# OpenCTD-V02.net
KiCad netlist of a schematic drawn in EAGLE
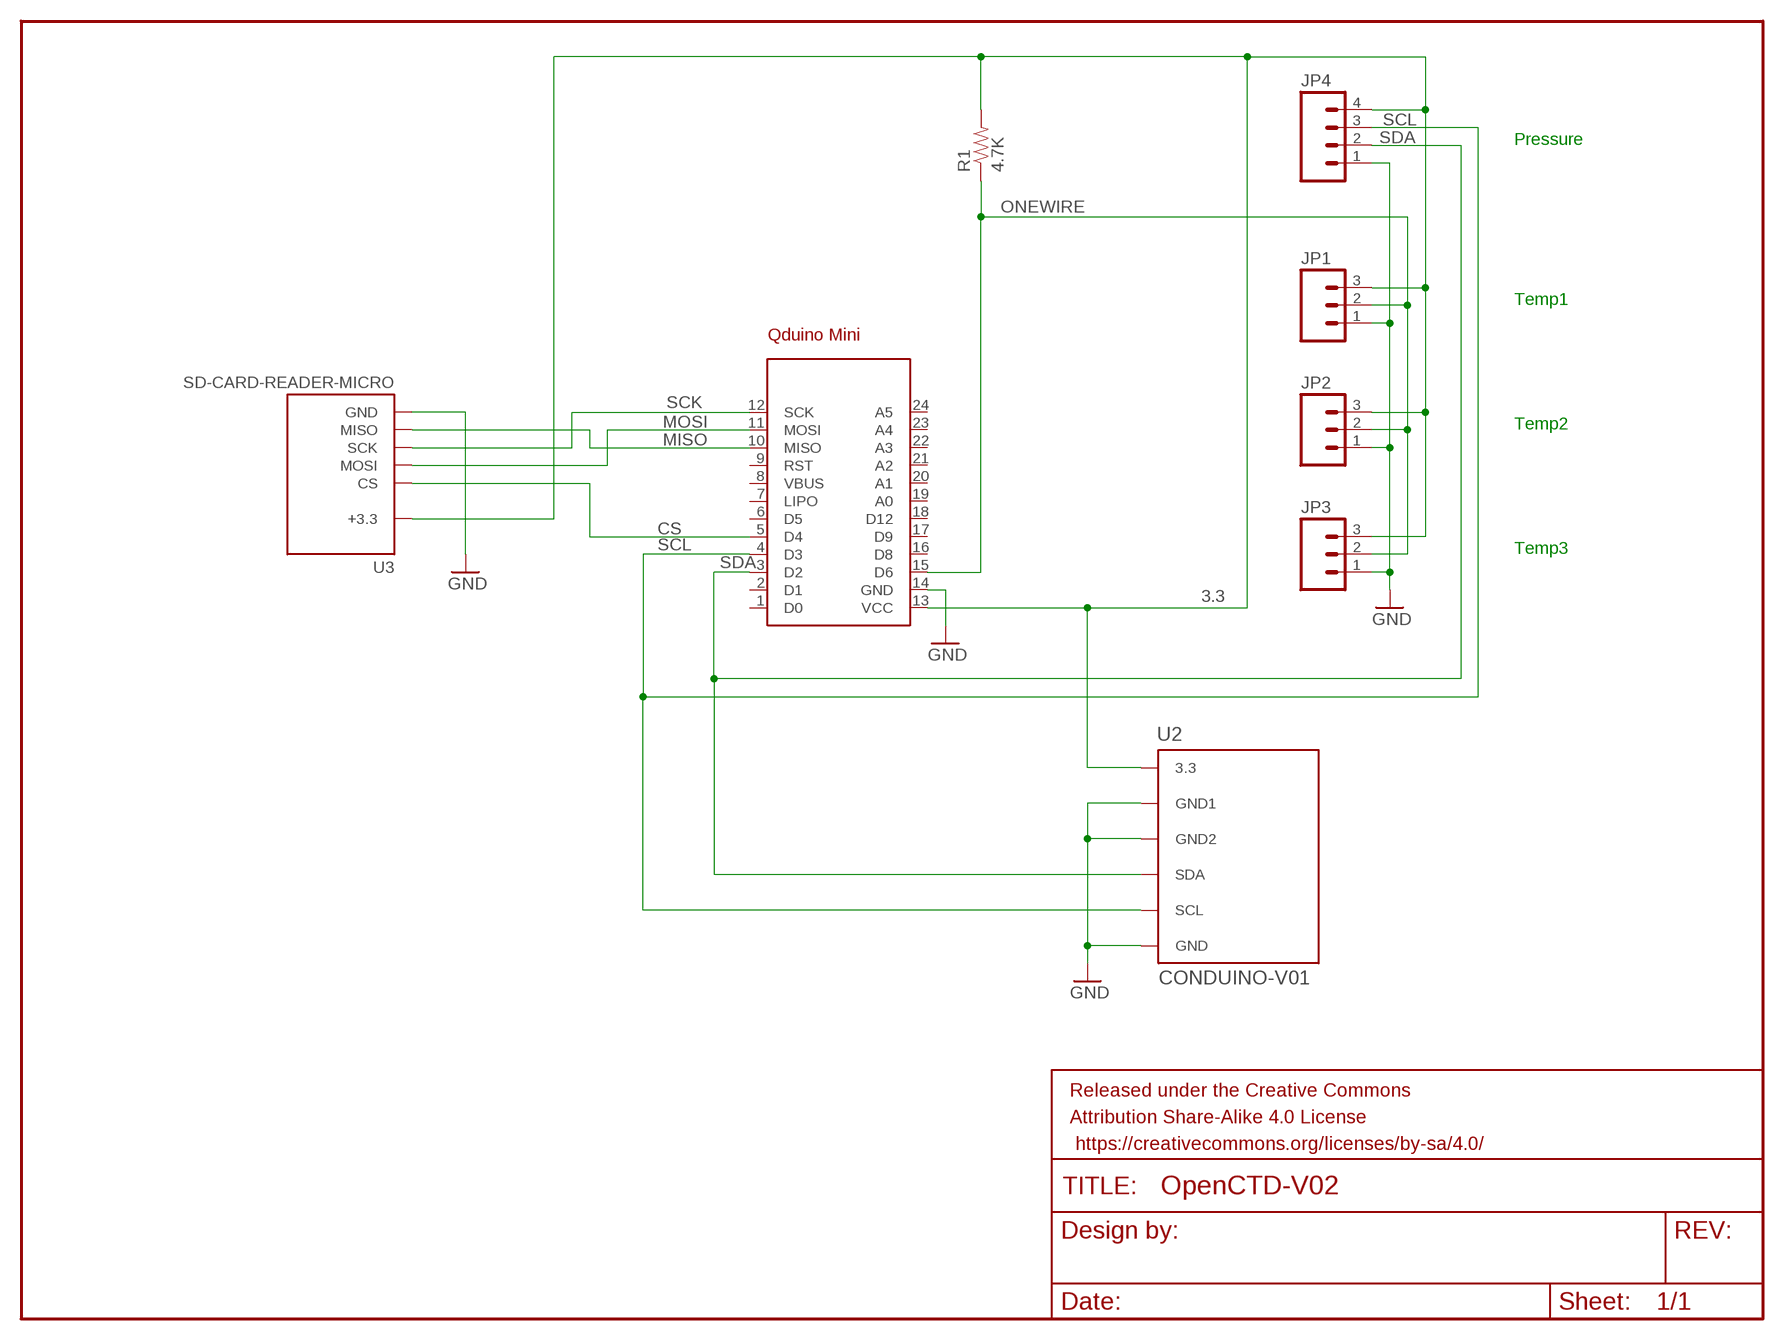
[diagram p0: schematic, sheet 1]

(export (version "E")
  (design (tool "Eeschema 10.0.6"))
  (components
    (comp (ref "FRAME1")
      (value "FRAME-LETTER")
      (footprint "eagle-import:CREATIVE_COMMONS")
      (libsource (lib "eagle-import") (part "FRAME-LETTER"))
    )
    (comp (ref "JP1")
      (value "M031X03_NO_SILK")
      (footprint "eagle-import:1X03_NO_SILK")
      (libsource (lib "eagle-import") (part "M031X03_NO_SILK"))
    )
    (comp (ref "JP2")
      (value "M031X03_NO_SILK")
      (footprint "eagle-import:1X03_NO_SILK")
      (libsource (lib "eagle-import") (part "M031X03_NO_SILK"))
    )
    (comp (ref "JP3")
      (value "M031X03_NO_SILK")
      (footprint "eagle-import:1X03_NO_SILK")
      (libsource (lib "eagle-import") (part "M031X03_NO_SILK"))
    )
    (comp (ref "JP4")
      (value "M041X04_NO_SILK")
      (footprint "eagle-import:1X04_NO_SILK")
      (libsource (lib "eagle-import") (part "M041X04_NO_SILK"))
    )
    (comp (ref "R1")
      (value "4.7K")
      (footprint "eagle-import:AXIAL-0.4")
      (libsource (lib "eagle-import") (part "RESISTORPTH-1/4W"))
    )
    (comp (ref "U1")
      (value "QDUINO_MINI")
      (footprint "eagle-import:QDUINO_MINI")
      (libsource (lib "eagle-import") (part "QDUINO_MINI"))
    )
    (comp (ref "U2")
      (value "CONDUINO-V01")
      (footprint "eagle-import:CONDUINO-V01")
      (libsource (lib "eagle-import") (part "CONDUINO-V01"))
    )
    (comp (ref "U3")
      (value "SD-CARD-READER-MICRO")
      (footprint "eagle-import:MICROSD_MOLEX")
      (libsource (lib "eagle-import") (part "SD-CARD-READER-MICRO"))
    )
  )
  (nets
    (net (code "1") (name "/3.3") (class "Default")
      (node (ref "JP1") (pin "3") (pinfunction "3_3") (pintype "passive"))
      (node (ref "JP2") (pin "3") (pinfunction "3_3") (pintype "passive"))
      (node (ref "JP3") (pin "3") (pinfunction "3_3") (pintype "passive"))
      (node (ref "JP4") (pin "4") (pinfunction "4_4") (pintype "passive"))
      (node (ref "R1") (pin "P$2") (pinfunction "2_P$2") (pintype "passive"))
      (node (ref "U1") (pin "13") (pinfunction "VCC_13") (pintype "bidirectional"))
      (node (ref "U2") (pin "6") (pinfunction "3.3_6") (pintype "bidirectional"))
      (node (ref "U3") (pin "P$4") (pinfunction "+3.3_P$4") (pintype "bidirectional"))
    )
    (net (code "2") (name "/CS") (class "Default")
      (node (ref "U1") (pin "5") (pinfunction "D4_5") (pintype "bidirectional"))
      (node (ref "U3") (pin "P$2") (pinfunction "CS_P$2") (pintype "bidirectional"))
    )
    (net (code "3") (name "/MISO") (class "Default")
      (node (ref "U1") (pin "10") (pinfunction "MISO_10") (pintype "bidirectional"))
      (node (ref "U3") (pin "P$7") (pinfunction "MISO_P$7") (pintype "bidirectional"))
    )
    (net (code "4") (name "/MOSI") (class "Default")
      (node (ref "U1") (pin "11") (pinfunction "MOSI_11") (pintype "bidirectional"))
      (node (ref "U3") (pin "P$3") (pinfunction "MOSI_P$3") (pintype "bidirectional"))
    )
    (net (code "5") (name "/ONEWIRE") (class "Default")
      (node (ref "JP1") (pin "2") (pinfunction "2_2") (pintype "passive"))
      (node (ref "JP2") (pin "2") (pinfunction "2_2") (pintype "passive"))
      (node (ref "JP3") (pin "2") (pinfunction "2_2") (pintype "passive"))
      (node (ref "R1") (pin "P$1") (pinfunction "1_P$1") (pintype "passive"))
      (node (ref "U1") (pin "15") (pinfunction "D6_15") (pintype "bidirectional"))
    )
    (net (code "6") (name "/SCK") (class "Default")
      (node (ref "U1") (pin "12") (pinfunction "SCK_12") (pintype "bidirectional"))
      (node (ref "U3") (pin "P$5") (pinfunction "SCK_P$5") (pintype "bidirectional"))
    )
    (net (code "7") (name "/SCL") (class "Default")
      (node (ref "JP4") (pin "3") (pinfunction "3_3") (pintype "passive"))
      (node (ref "U1") (pin "4") (pinfunction "D3_4") (pintype "bidirectional"))
      (node (ref "U2") (pin "1") (pinfunction "SCL_1") (pintype "bidirectional"))
    )
    (net (code "8") (name "/SDA") (class "Default")
      (node (ref "JP4") (pin "2") (pinfunction "2_2") (pintype "passive"))
      (node (ref "U1") (pin "3") (pinfunction "D2_3") (pintype "bidirectional"))
      (node (ref "U2") (pin "2") (pinfunction "SDA_2") (pintype "bidirectional"))
    )
    (net (code "9") (name "GND") (class "Default")
      (node (ref "JP1") (pin "1") (pinfunction "1_1") (pintype "passive"))
      (node (ref "JP2") (pin "1") (pinfunction "1_1") (pintype "passive"))
      (node (ref "JP3") (pin "1") (pinfunction "1_1") (pintype "passive"))
      (node (ref "JP4") (pin "1") (pinfunction "1_1") (pintype "passive"))
      (node (ref "U1") (pin "14") (pinfunction "GND_14") (pintype "bidirectional"))
      (node (ref "U2") (pin "3") (pinfunction "GND_3") (pintype "bidirectional"))
      (node (ref "U2") (pin "4") (pinfunction "GND1_4") (pintype "bidirectional"))
      (node (ref "U2") (pin "5") (pinfunction "GND2_5") (pintype "bidirectional"))
      (node (ref "U3") (pin "P$10") (pinfunction "GND_P$10") (pintype "bidirectional"))
      (node (ref "U3") (pin "P$11") (pinfunction "GND_P$11") (pintype "bidirectional"))
      (node (ref "U3") (pin "P$12") (pinfunction "GND_P$12") (pintype "bidirectional"))
      (node (ref "U3") (pin "P$6") (pinfunction "GND_P$6") (pintype "bidirectional"))
      (node (ref "U3") (pin "P$9") (pinfunction "GND_P$9") (pintype "bidirectional"))
    )
    (net (code "10") (name "unconnected-(U1-A0-Pad19)") (class "Default")
      (node (ref "U1") (pin "19") (pinfunction "A0_19") (pintype "bidirectional"))
    )
    (net (code "11") (name "unconnected-(U1-A1-Pad20)") (class "Default")
      (node (ref "U1") (pin "20") (pinfunction "A1_20") (pintype "bidirectional"))
    )
    (net (code "12") (name "unconnected-(U1-A2-Pad21)") (class "Default")
      (node (ref "U1") (pin "21") (pinfunction "A2_21") (pintype "bidirectional"))
    )
    (net (code "13") (name "unconnected-(U1-A3-Pad22)") (class "Default")
      (node (ref "U1") (pin "22") (pinfunction "A3_22") (pintype "bidirectional"))
    )
    (net (code "14") (name "unconnected-(U1-A4-Pad23)") (class "Default")
      (node (ref "U1") (pin "23") (pinfunction "A4_23") (pintype "bidirectional"))
    )
    (net (code "15") (name "unconnected-(U1-A5-Pad24)") (class "Default")
      (node (ref "U1") (pin "24") (pinfunction "A5_24") (pintype "bidirectional"))
    )
    (net (code "16") (name "unconnected-(U1-D0-Pad1)") (class "Default")
      (node (ref "U1") (pin "1") (pinfunction "D0_1") (pintype "bidirectional"))
    )
    (net (code "17") (name "unconnected-(U1-D1-Pad2)") (class "Default")
      (node (ref "U1") (pin "2") (pinfunction "D1_2") (pintype "bidirectional"))
    )
    (net (code "18") (name "unconnected-(U1-D5-Pad6)") (class "Default")
      (node (ref "U1") (pin "6") (pinfunction "D5_6") (pintype "bidirectional"))
    )
    (net (code "19") (name "unconnected-(U1-D8-Pad16)") (class "Default")
      (node (ref "U1") (pin "16") (pinfunction "D8_16") (pintype "bidirectional"))
    )
    (net (code "20") (name "unconnected-(U1-D9-Pad17)") (class "Default")
      (node (ref "U1") (pin "17") (pinfunction "D9_17") (pintype "bidirectional"))
    )
    (net (code "21") (name "unconnected-(U1-D12-Pad18)") (class "Default")
      (node (ref "U1") (pin "18") (pinfunction "D12_18") (pintype "bidirectional"))
    )
    (net (code "22") (name "unconnected-(U1-LIPO-Pad7)") (class "Default")
      (node (ref "U1") (pin "7") (pinfunction "LIPO_7") (pintype "bidirectional"))
    )
    (net (code "23") (name "unconnected-(U1-RST-Pad9)") (class "Default")
      (node (ref "U1") (pin "9") (pinfunction "RST_9") (pintype "bidirectional"))
    )
    (net (code "24") (name "unconnected-(U1-VBUS-Pad8)") (class "Default")
      (node (ref "U1") (pin "8") (pinfunction "VBUS_8") (pintype "bidirectional"))
    )
  )
)
